# TMC2100-TA-T_Breakout.net
KiCad netlist of a schematic drawn in Altium Designer
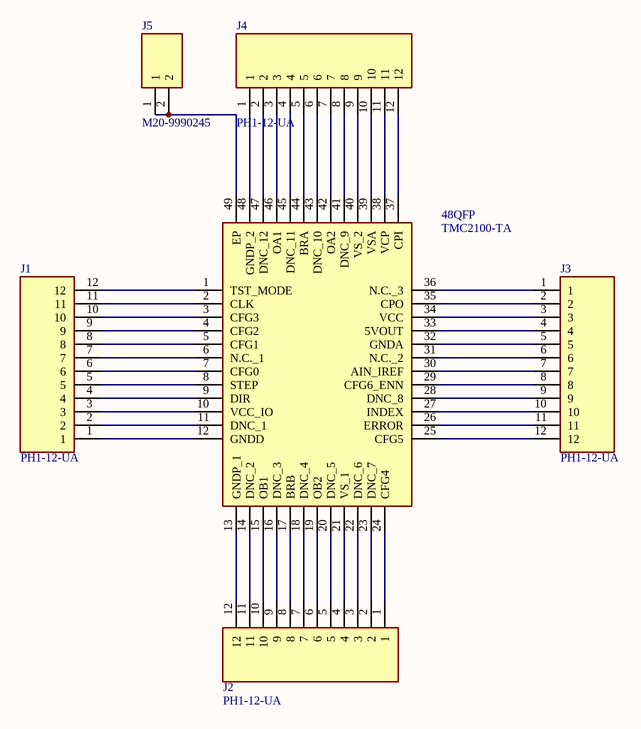
[diagram p0: TMC2100-TA-T_Breakout.SchDoc]

(export (version "E")
  (design (tool "Eeschema 10.0.6"))
  (components
    (comp (ref "48QFP")
      (value "TMC2100-TA")
      (footprint "SamacSys:QFP50P900X900X120-49N")
      (description "Integrated Circuit")
      (fields (field (name "MOUSER PART NUMBER") "700-TMC2100TA"))
      (libsource (lib "*") (part "TMC2100-TA"))
    )
    (comp (ref "J1")
      (value "PH1-12-UA")
      (footprint "SamacSys:HDRV12W64P0X254_1X12_3048X250X847P")
      (description "Connector")
      (fields (field (name "MOUSER PART NUMBER") "737-PH1-12-UA"))
      (libsource (lib "") (part "PH1-12-UA_1"))
    )
    (comp (ref "J2")
      (value "PH1-12-UA")
      (footprint "SamacSys:HDRV12W64P0X254_1X12_3048X250X847P")
      (description "Connector")
      (fields (field (name "MOUSER PART NUMBER") "737-PH1-12-UA"))
      (libsource (lib "") (part "PH1-12-UA_2"))
    )
    (comp (ref "J3")
      (value "PH1-12-UA")
      (footprint "SamacSys:HDRV12W64P0X254_1X12_3048X250X847P")
      (description "Connector")
      (fields (field (name "MOUSER PART NUMBER") "737-PH1-12-UA"))
      (libsource (lib "") (part "PH1-12-UA_3"))
    )
    (comp (ref "J4")
      (value "PH1-12-UA")
      (footprint "SamacSys:HDRV12W64P0X254_1X12_3048X250X847P")
      (description "Connector")
      (fields (field (name "MOUSER PART NUMBER") "737-PH1-12-UA"))
      (libsource (lib "*") (part "PH1-12-UA"))
    )
    (comp (ref "J5")
      (value "M20-9990245")
      (footprint "SamacSys:HDRV2W64P0X254_1X2_508X254X864P")
      (description "Connector")
      (fields (field (name "MOUSER PART NUMBER") "855-M20-9990245"))
      (libsource (lib "*") (part "M20-9990245"))
    )
  )
  (nets
    (net (code "1") (name "Net-(48QFP-5VOUT)") (class "Default")
      (node (ref "48QFP") (pin "33") (pinfunction "5VOUT_33") (pintype "passive"))
      (node (ref "J3") (pin "4") (pinfunction "4_4") (pintype "passive"))
    )
    (net (code "2") (name "Net-(48QFP-AIN_IREF)") (class "Default")
      (node (ref "48QFP") (pin "30") (pinfunction "AIN_IREF_30") (pintype "passive"))
      (node (ref "J3") (pin "7") (pinfunction "7_7") (pintype "passive"))
    )
    (net (code "3") (name "Net-(48QFP-BRA)") (class "Default")
      (node (ref "48QFP") (pin "44") (pinfunction "BRA_44") (pintype "passive"))
      (node (ref "J4") (pin "5") (pinfunction "5_5") (pintype "passive"))
    )
    (net (code "4") (name "Net-(48QFP-BRB)") (class "Default")
      (node (ref "48QFP") (pin "17") (pinfunction "BRB_17") (pintype "passive"))
      (node (ref "J2") (pin "8") (pinfunction "8_8") (pintype "passive"))
    )
    (net (code "5") (name "Net-(48QFP-CFG0)") (class "Default")
      (node (ref "48QFP") (pin "7") (pinfunction "CFG0_7") (pintype "passive"))
      (node (ref "J1") (pin "6") (pinfunction "6_6") (pintype "passive"))
    )
    (net (code "6") (name "Net-(48QFP-CFG1)") (class "Default")
      (node (ref "48QFP") (pin "5") (pinfunction "CFG1_5") (pintype "passive"))
      (node (ref "J1") (pin "8") (pinfunction "8_8") (pintype "passive"))
    )
    (net (code "7") (name "Net-(48QFP-CFG2)") (class "Default")
      (node (ref "48QFP") (pin "4") (pinfunction "CFG2_4") (pintype "passive"))
      (node (ref "J1") (pin "9") (pinfunction "9_9") (pintype "passive"))
    )
    (net (code "8") (name "Net-(48QFP-CFG3)") (class "Default")
      (node (ref "48QFP") (pin "3") (pinfunction "CFG3_3") (pintype "passive"))
      (node (ref "J1") (pin "10") (pinfunction "10_10") (pintype "passive"))
    )
    (net (code "9") (name "Net-(48QFP-CFG4)") (class "Default")
      (node (ref "48QFP") (pin "24") (pinfunction "CFG4_24") (pintype "passive"))
      (node (ref "J2") (pin "1") (pinfunction "1_1") (pintype "passive"))
    )
    (net (code "10") (name "Net-(48QFP-CFG5)") (class "Default")
      (node (ref "48QFP") (pin "25") (pinfunction "CFG5_25") (pintype "passive"))
      (node (ref "J3") (pin "12") (pinfunction "12_12") (pintype "passive"))
    )
    (net (code "11") (name "Net-(48QFP-CFG6_ENN)") (class "Default")
      (node (ref "48QFP") (pin "29") (pinfunction "CFG6_ENN_29") (pintype "passive"))
      (node (ref "J3") (pin "8") (pinfunction "8_8") (pintype "passive"))
    )
    (net (code "12") (name "Net-(48QFP-CLK)") (class "Default")
      (node (ref "48QFP") (pin "2") (pinfunction "CLK_2") (pintype "passive"))
      (node (ref "J1") (pin "11") (pinfunction "11_11") (pintype "passive"))
    )
    (net (code "13") (name "Net-(48QFP-CPI)") (class "Default")
      (node (ref "48QFP") (pin "37") (pinfunction "CPI_37") (pintype "passive"))
      (node (ref "J4") (pin "12") (pinfunction "12_12") (pintype "passive"))
    )
    (net (code "14") (name "Net-(48QFP-CPO)") (class "Default")
      (node (ref "48QFP") (pin "35") (pinfunction "CPO_35") (pintype "passive"))
      (node (ref "J3") (pin "2") (pinfunction "2_2") (pintype "passive"))
    )
    (net (code "15") (name "Net-(48QFP-DIR)") (class "Default")
      (node (ref "48QFP") (pin "9") (pinfunction "DIR_9") (pintype "passive"))
      (node (ref "J1") (pin "4") (pinfunction "4_4") (pintype "passive"))
    )
    (net (code "16") (name "Net-(48QFP-DNC_1)") (class "Default")
      (node (ref "48QFP") (pin "11") (pinfunction "DNC_1_11") (pintype "passive"))
      (node (ref "J1") (pin "2") (pinfunction "2_2") (pintype "passive"))
    )
    (net (code "17") (name "Net-(48QFP-DNC_2)") (class "Default")
      (node (ref "48QFP") (pin "14") (pinfunction "DNC_2_14") (pintype "passive"))
      (node (ref "J2") (pin "11") (pinfunction "11_11") (pintype "passive"))
    )
    (net (code "18") (name "Net-(48QFP-DNC_3)") (class "Default")
      (node (ref "48QFP") (pin "16") (pinfunction "DNC_3_16") (pintype "passive"))
      (node (ref "J2") (pin "9") (pinfunction "9_9") (pintype "passive"))
    )
    (net (code "19") (name "Net-(48QFP-DNC_4)") (class "Default")
      (node (ref "48QFP") (pin "18") (pinfunction "DNC_4_18") (pintype "passive"))
      (node (ref "J2") (pin "7") (pinfunction "7_7") (pintype "passive"))
    )
    (net (code "20") (name "Net-(48QFP-DNC_5)") (class "Default")
      (node (ref "48QFP") (pin "20") (pinfunction "DNC_5_20") (pintype "passive"))
      (node (ref "J2") (pin "5") (pinfunction "5_5") (pintype "passive"))
    )
    (net (code "21") (name "Net-(48QFP-DNC_6)") (class "Default")
      (node (ref "48QFP") (pin "22") (pinfunction "DNC_6_22") (pintype "passive"))
      (node (ref "J2") (pin "3") (pinfunction "3_3") (pintype "passive"))
    )
    (net (code "22") (name "Net-(48QFP-DNC_7)") (class "Default")
      (node (ref "48QFP") (pin "23") (pinfunction "DNC_7_23") (pintype "passive"))
      (node (ref "J2") (pin "2") (pinfunction "2_2") (pintype "passive"))
    )
    (net (code "23") (name "Net-(48QFP-DNC_8)") (class "Default")
      (node (ref "48QFP") (pin "28") (pinfunction "DNC_8_28") (pintype "passive"))
      (node (ref "J3") (pin "9") (pinfunction "9_9") (pintype "passive"))
    )
    (net (code "24") (name "Net-(48QFP-DNC_9)") (class "Default")
      (node (ref "48QFP") (pin "41") (pinfunction "DNC_9_41") (pintype "passive"))
      (node (ref "J4") (pin "8") (pinfunction "8_8") (pintype "passive"))
    )
    (net (code "25") (name "Net-(48QFP-DNC_10)") (class "Default")
      (node (ref "48QFP") (pin "43") (pinfunction "DNC_10_43") (pintype "passive"))
      (node (ref "J4") (pin "6") (pinfunction "6_6") (pintype "passive"))
    )
    (net (code "26") (name "Net-(48QFP-DNC_11)") (class "Default")
      (node (ref "48QFP") (pin "45") (pinfunction "DNC_11_45") (pintype "passive"))
      (node (ref "J4") (pin "4") (pinfunction "4_4") (pintype "passive"))
    )
    (net (code "27") (name "Net-(48QFP-DNC_12)") (class "Default")
      (node (ref "48QFP") (pin "47") (pinfunction "DNC_12_47") (pintype "passive"))
      (node (ref "J4") (pin "2") (pinfunction "2_2") (pintype "passive"))
    )
    (net (code "28") (name "Net-(48QFP-EP)") (class "Default")
      (node (ref "48QFP") (pin "49") (pinfunction "EP_49") (pintype "passive"))
      (node (ref "J5") (pin "1") (pinfunction "1_1") (pintype "passive"))
      (node (ref "J5") (pin "2") (pinfunction "2_2") (pintype "passive"))
    )
    (net (code "29") (name "Net-(48QFP-ERROR)") (class "Default")
      (node (ref "48QFP") (pin "26") (pinfunction "ERROR_26") (pintype "passive"))
      (node (ref "J3") (pin "11") (pinfunction "11_11") (pintype "passive"))
    )
    (net (code "30") (name "Net-(48QFP-GNDA)") (class "Default")
      (node (ref "48QFP") (pin "32") (pinfunction "GNDA_32") (pintype "passive"))
      (node (ref "J3") (pin "5") (pinfunction "5_5") (pintype "passive"))
    )
    (net (code "31") (name "Net-(48QFP-GNDD)") (class "Default")
      (node (ref "48QFP") (pin "12") (pinfunction "GNDD_12") (pintype "passive"))
      (node (ref "J1") (pin "1") (pinfunction "1_1") (pintype "passive"))
    )
    (net (code "32") (name "Net-(48QFP-GNDP_1)") (class "Default")
      (node (ref "48QFP") (pin "13") (pinfunction "GNDP_1_13") (pintype "passive"))
      (node (ref "J2") (pin "12") (pinfunction "12_12") (pintype "passive"))
    )
    (net (code "33") (name "Net-(48QFP-GNDP_2)") (class "Default")
      (node (ref "48QFP") (pin "48") (pinfunction "GNDP_2_48") (pintype "passive"))
      (node (ref "J4") (pin "1") (pinfunction "1_1") (pintype "passive"))
    )
    (net (code "34") (name "Net-(48QFP-INDEX)") (class "Default")
      (node (ref "48QFP") (pin "27") (pinfunction "INDEX_27") (pintype "passive"))
      (node (ref "J3") (pin "10") (pinfunction "10_10") (pintype "passive"))
    )
    (net (code "35") (name "Net-(48QFP-N.C._1)") (class "Default")
      (node (ref "48QFP") (pin "6") (pinfunction "N.C._1_6") (pintype "passive"))
      (node (ref "J1") (pin "7") (pinfunction "7_7") (pintype "passive"))
    )
    (net (code "36") (name "Net-(48QFP-N.C._2)") (class "Default")
      (node (ref "48QFP") (pin "31") (pinfunction "N.C._2_31") (pintype "passive"))
      (node (ref "J3") (pin "6") (pinfunction "6_6") (pintype "passive"))
    )
    (net (code "37") (name "Net-(48QFP-N.C._3)") (class "Default")
      (node (ref "48QFP") (pin "36") (pinfunction "N.C._3_36") (pintype "passive"))
      (node (ref "J3") (pin "1") (pinfunction "1_1") (pintype "passive"))
    )
    (net (code "38") (name "Net-(48QFP-OA1)") (class "Default")
      (node (ref "48QFP") (pin "46") (pinfunction "OA1_46") (pintype "passive"))
      (node (ref "J4") (pin "3") (pinfunction "3_3") (pintype "passive"))
    )
    (net (code "39") (name "Net-(48QFP-OA2)") (class "Default")
      (node (ref "48QFP") (pin "42") (pinfunction "OA2_42") (pintype "passive"))
      (node (ref "J4") (pin "7") (pinfunction "7_7") (pintype "passive"))
    )
    (net (code "40") (name "Net-(48QFP-OB1)") (class "Default")
      (node (ref "48QFP") (pin "15") (pinfunction "OB1_15") (pintype "passive"))
      (node (ref "J2") (pin "10") (pinfunction "10_10") (pintype "passive"))
    )
    (net (code "41") (name "Net-(48QFP-OB2)") (class "Default")
      (node (ref "48QFP") (pin "19") (pinfunction "OB2_19") (pintype "passive"))
      (node (ref "J2") (pin "6") (pinfunction "6_6") (pintype "passive"))
    )
    (net (code "42") (name "Net-(48QFP-STEP)") (class "Default")
      (node (ref "48QFP") (pin "8") (pinfunction "STEP_8") (pintype "passive"))
      (node (ref "J1") (pin "5") (pinfunction "5_5") (pintype "passive"))
    )
    (net (code "43") (name "Net-(48QFP-TST_MODE)") (class "Default")
      (node (ref "48QFP") (pin "1") (pinfunction "TST_MODE_1") (pintype "passive"))
      (node (ref "J1") (pin "12") (pinfunction "12_12") (pintype "passive"))
    )
    (net (code "44") (name "Net-(48QFP-VCC)") (class "Default")
      (node (ref "48QFP") (pin "34") (pinfunction "VCC_34") (pintype "passive"))
      (node (ref "J3") (pin "3") (pinfunction "3_3") (pintype "passive"))
    )
    (net (code "45") (name "Net-(48QFP-VCC_IO)") (class "Default")
      (node (ref "48QFP") (pin "10") (pinfunction "VCC_IO_10") (pintype "passive"))
      (node (ref "J1") (pin "3") (pinfunction "3_3") (pintype "passive"))
    )
    (net (code "46") (name "Net-(48QFP-VCP)") (class "Default")
      (node (ref "48QFP") (pin "38") (pinfunction "VCP_38") (pintype "passive"))
      (node (ref "J4") (pin "11") (pinfunction "11_11") (pintype "passive"))
    )
    (net (code "47") (name "Net-(48QFP-VSA)") (class "Default")
      (node (ref "48QFP") (pin "39") (pinfunction "VSA_39") (pintype "passive"))
      (node (ref "J4") (pin "10") (pinfunction "10_10") (pintype "passive"))
    )
    (net (code "48") (name "Net-(48QFP-VS_1)") (class "Default")
      (node (ref "48QFP") (pin "21") (pinfunction "VS_1_21") (pintype "passive"))
      (node (ref "J2") (pin "4") (pinfunction "4_4") (pintype "passive"))
    )
    (net (code "49") (name "Net-(48QFP-VS_2)") (class "Default")
      (node (ref "48QFP") (pin "40") (pinfunction "VS_2_40") (pintype "passive"))
      (node (ref "J4") (pin "9") (pinfunction "9_9") (pintype "passive"))
    )
  )
)
